# memory.net
KiCad netlist of a schematic drawn in Altium Designer
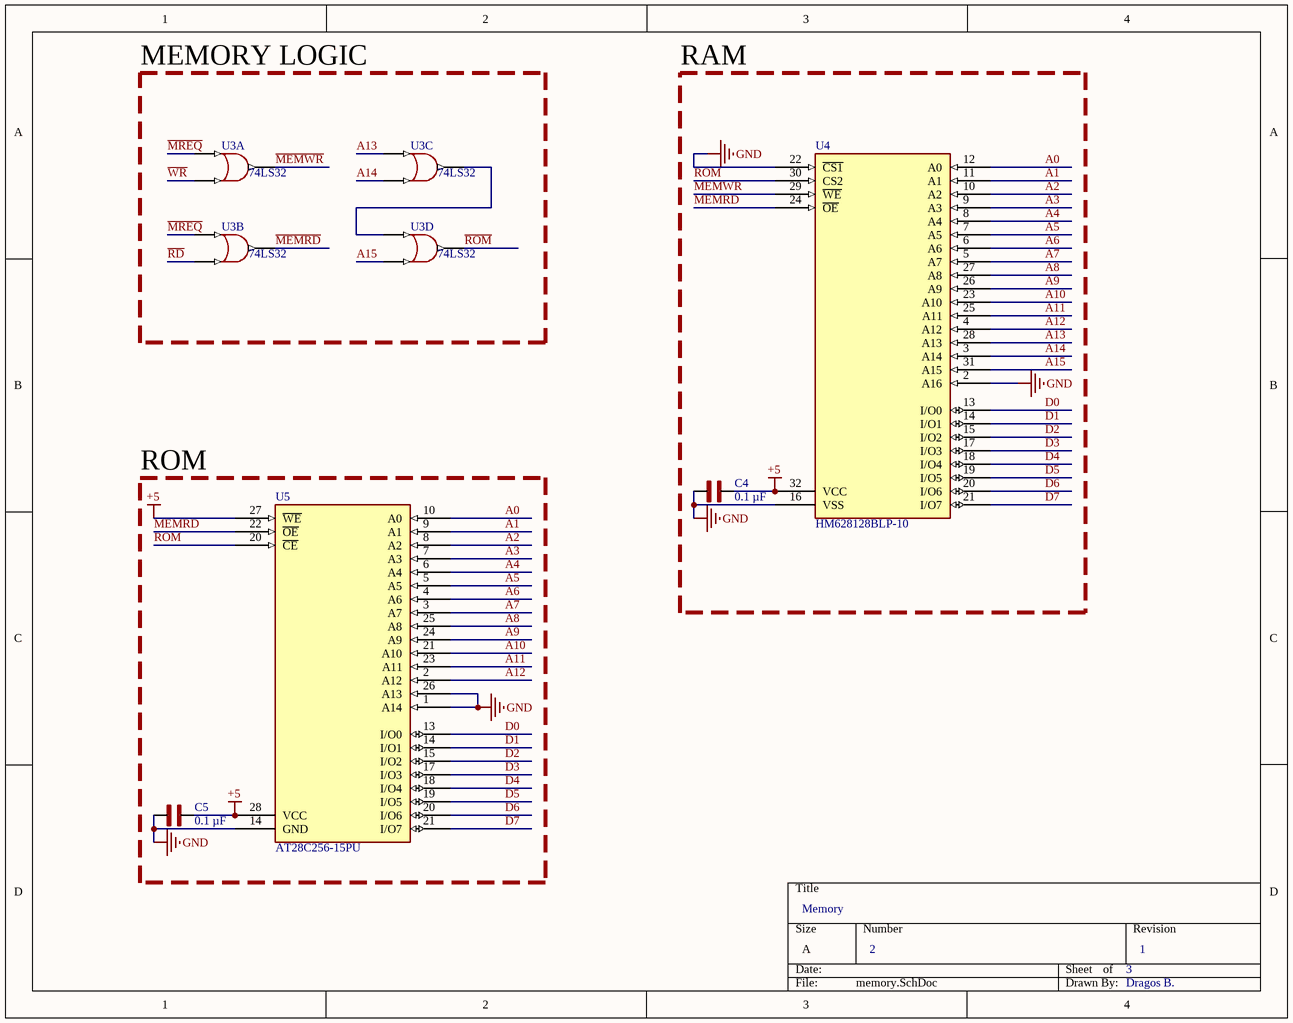
[diagram p0: memory.SchDoc]

(export (version "E")
  (design (tool "Eeschema 10.0.6"))
  (components
    (comp (ref "C4")
      (value "0.1 µF")
      (footprint "Capacitor")
      (fields (field (name "MP") "ECWFG70105K") (field (name "MF") "Panasonic"))
      (libsource (lib "components") (part "CAPACITOR"))
    )
    (comp (ref "C5")
      (value "0.1 µF")
      (footprint "Capacitor")
      (fields (field (name "MP") "ECWFG70105K") (field (name "MF") "Panasonic"))
      (libsource (lib "components") (part "CAPACITOR"))
    )
    (comp (ref "U3") (value "74LS32") (footprint "DIP14") (libsource (lib "components") (part "74LS32")))
    (comp (ref "U4")
      (value "HM628128BLP-10")
      (footprint "DIP32")
      (libsource (lib "components") (part "HM628128BLP-10"))
    )
    (comp (ref "U5")
      (value "AT28C256-15PU")
      (footprint "DIP28")
      (libsource (lib "components") (part "AT28C256-15PU"))
    )
  )
  (nets
    (net (code "1") (name "+5") (class "Default")
      (node (ref "C4") (pin "2") (pinfunction "2_2") (pintype "passive"))
      (node (ref "C5") (pin "2") (pinfunction "2_2") (pintype "passive"))
      (node (ref "U4") (pin "32") (pinfunction "VCC_32") (pintype "power_in"))
      (node (ref "U5") (pin "27") (pinfunction "WE_27") (pintype "input"))
      (node (ref "U5") (pin "28") (pinfunction "VCC_28") (pintype "power_in"))
    )
    (net (code "2") (name "/A0") (class "Default")
      (node (ref "U4") (pin "12") (pinfunction "A0_12") (pintype "input"))
      (node (ref "U5") (pin "10") (pinfunction "A0_10") (pintype "input"))
    )
    (net (code "3") (name "/A1") (class "Default")
      (node (ref "U4") (pin "11") (pinfunction "A1_11") (pintype "input"))
      (node (ref "U5") (pin "9") (pinfunction "A1_9") (pintype "input"))
    )
    (net (code "4") (name "/A2") (class "Default")
      (node (ref "U4") (pin "10") (pinfunction "A2_10") (pintype "input"))
      (node (ref "U5") (pin "8") (pinfunction "A2_8") (pintype "input"))
    )
    (net (code "5") (name "/A3") (class "Default")
      (node (ref "U4") (pin "9") (pinfunction "A3_9") (pintype "input"))
      (node (ref "U5") (pin "7") (pinfunction "A3_7") (pintype "input"))
    )
    (net (code "6") (name "/A4") (class "Default")
      (node (ref "U4") (pin "8") (pinfunction "A4_8") (pintype "input"))
      (node (ref "U5") (pin "6") (pinfunction "A4_6") (pintype "input"))
    )
    (net (code "7") (name "/A5") (class "Default")
      (node (ref "U4") (pin "7") (pinfunction "A5_7") (pintype "input"))
      (node (ref "U5") (pin "5") (pinfunction "A5_5") (pintype "input"))
    )
    (net (code "8") (name "/A6") (class "Default")
      (node (ref "U4") (pin "6") (pinfunction "A6_6") (pintype "input"))
      (node (ref "U5") (pin "4") (pinfunction "A6_4") (pintype "input"))
    )
    (net (code "9") (name "/A7") (class "Default")
      (node (ref "U4") (pin "5") (pinfunction "A7_5") (pintype "input"))
      (node (ref "U5") (pin "3") (pinfunction "A7_3") (pintype "input"))
    )
    (net (code "10") (name "/A8") (class "Default")
      (node (ref "U4") (pin "27") (pinfunction "A8_27") (pintype "input"))
      (node (ref "U5") (pin "25") (pinfunction "A8_25") (pintype "input"))
    )
    (net (code "11") (name "/A9") (class "Default")
      (node (ref "U4") (pin "26") (pinfunction "A9_26") (pintype "input"))
      (node (ref "U5") (pin "24") (pinfunction "A9_24") (pintype "input"))
    )
    (net (code "12") (name "/A10") (class "Default")
      (node (ref "U4") (pin "23") (pinfunction "A10_23") (pintype "input"))
      (node (ref "U5") (pin "21") (pinfunction "A10_21") (pintype "input"))
    )
    (net (code "13") (name "/A11") (class "Default")
      (node (ref "U4") (pin "25") (pinfunction "A11_25") (pintype "input"))
      (node (ref "U5") (pin "23") (pinfunction "A11_23") (pintype "input"))
    )
    (net (code "14") (name "/A12") (class "Default")
      (node (ref "U4") (pin "4") (pinfunction "A12_4") (pintype "input"))
      (node (ref "U5") (pin "2") (pinfunction "A12_2") (pintype "input"))
    )
    (net (code "15") (name "/A13") (class "Default")
      (node (ref "U3") (pin "9") (pinfunction "A3_9") (pintype "input"))
      (node (ref "U4") (pin "28") (pinfunction "A13_28") (pintype "input"))
    )
    (net (code "16") (name "/A14") (class "Default")
      (node (ref "U3") (pin "10") (pinfunction "B3_10") (pintype "input"))
      (node (ref "U4") (pin "3") (pinfunction "A14_3") (pintype "input"))
    )
    (net (code "17") (name "/A15") (class "Default")
      (node (ref "U3") (pin "13") (pinfunction "B4_13") (pintype "input"))
      (node (ref "U4") (pin "31") (pinfunction "A15_31") (pintype "input"))
    )
    (net (code "18") (name "/D0") (class "Default")
      (node (ref "U4") (pin "13") (pinfunction "I/O0_13") (pintype "bidirectional"))
      (node (ref "U5") (pin "13") (pinfunction "I/O0_13") (pintype "bidirectional"))
    )
    (net (code "19") (name "/D1") (class "Default")
      (node (ref "U4") (pin "14") (pinfunction "I/O1_14") (pintype "bidirectional"))
      (node (ref "U5") (pin "14") (pinfunction "I/O1_14") (pintype "bidirectional"))
    )
    (net (code "20") (name "/D2") (class "Default")
      (node (ref "U4") (pin "15") (pinfunction "I/O2_15") (pintype "bidirectional"))
      (node (ref "U5") (pin "15") (pinfunction "I/O2_15") (pintype "bidirectional"))
    )
    (net (code "21") (name "/D3") (class "Default")
      (node (ref "U4") (pin "17") (pinfunction "I/O3_17") (pintype "bidirectional"))
      (node (ref "U5") (pin "17") (pinfunction "I/O3_17") (pintype "bidirectional"))
    )
    (net (code "22") (name "/D4") (class "Default")
      (node (ref "U4") (pin "18") (pinfunction "I/O4_18") (pintype "bidirectional"))
      (node (ref "U5") (pin "18") (pinfunction "I/O4_18") (pintype "bidirectional"))
    )
    (net (code "23") (name "/D5") (class "Default")
      (node (ref "U4") (pin "19") (pinfunction "I/O5_19") (pintype "bidirectional"))
      (node (ref "U5") (pin "19") (pinfunction "I/O5_19") (pintype "bidirectional"))
    )
    (net (code "24") (name "/D6") (class "Default")
      (node (ref "U4") (pin "20") (pinfunction "I/O6_20") (pintype "bidirectional"))
      (node (ref "U5") (pin "20") (pinfunction "I/O6_20") (pintype "bidirectional"))
    )
    (net (code "25") (name "/D7") (class "Default")
      (node (ref "U4") (pin "21") (pinfunction "I/O7_21") (pintype "bidirectional"))
      (node (ref "U5") (pin "21") (pinfunction "I/O7_21") (pintype "bidirectional"))
    )
    (net (code "26") (name "/MEMRD") (class "Default")
      (node (ref "U3") (pin "6") (pinfunction "Y2_6") (pintype "output"))
      (node (ref "U4") (pin "24") (pinfunction "OE_24") (pintype "input"))
      (node (ref "U5") (pin "22") (pinfunction "OE_22") (pintype "input"))
    )
    (net (code "27") (name "/MEMWR") (class "Default")
      (node (ref "U3") (pin "3") (pinfunction "Y1_3") (pintype "output"))
      (node (ref "U4") (pin "29") (pinfunction "WE_29") (pintype "input"))
    )
    (net (code "28") (name "/MREQ") (class "Default")
      (node (ref "U3") (pin "1") (pinfunction "A1_1") (pintype "input"))
      (node (ref "U3") (pin "4") (pinfunction "A2_4") (pintype "input"))
    )
    (net (code "29") (name "/RD") (class "Default")
      (node (ref "U3") (pin "5") (pinfunction "B2_5") (pintype "input"))
    )
    (net (code "30") (name "/ROM") (class "Default")
      (node (ref "U3") (pin "11") (pinfunction "Y4_11") (pintype "output"))
      (node (ref "U4") (pin "30") (pinfunction "CS2_30") (pintype "input"))
      (node (ref "U5") (pin "20") (pinfunction "CE_20") (pintype "input"))
    )
    (net (code "31") (name "/WR") (class "Default")
      (node (ref "U3") (pin "2") (pinfunction "B1_2") (pintype "input"))
    )
    (net (code "32") (name "GND") (class "Default")
      (node (ref "C4") (pin "1") (pinfunction "1_1") (pintype "passive"))
      (node (ref "C5") (pin "1") (pinfunction "1_1") (pintype "passive"))
      (node (ref "U4") (pin "16") (pinfunction "VSS_16") (pintype "power_in"))
      (node (ref "U4") (pin "2") (pinfunction "A16_2") (pintype "input"))
      (node (ref "U4") (pin "22") (pinfunction "CS1_22") (pintype "input"))
      (node (ref "U5") (pin "1") (pinfunction "A14_1") (pintype "input"))
      (node (ref "U5") (pin "14") (pinfunction "GND_14") (pintype "power_in"))
      (node (ref "U5") (pin "26") (pinfunction "A13_26") (pintype "input"))
    )
    (net (code "33") (name "Net-(U3C-Y3)") (class "Default")
      (node (ref "U3") (pin "12") (pinfunction "A4_12") (pintype "input"))
      (node (ref "U3") (pin "8") (pinfunction "Y3_8") (pintype "output"))
    )
  )
)
